# audio_board.net
KiCad netlist of a schematic drawn in EAGLE
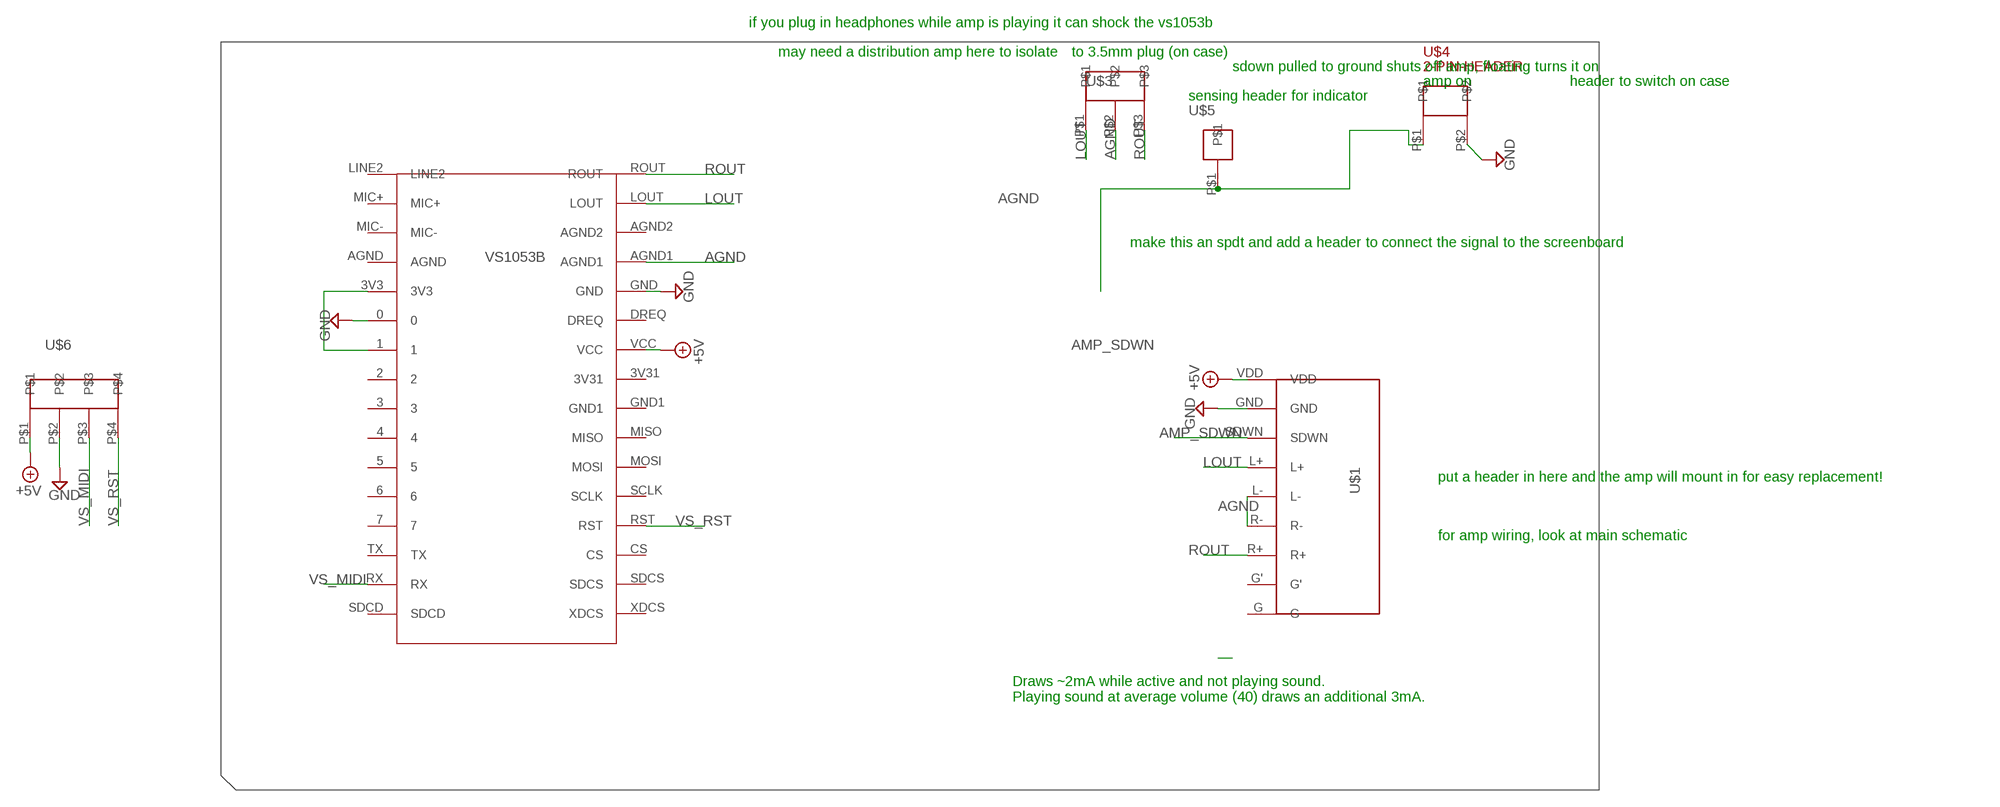
[diagram p0: schematic, sheet 1]

(export (version "E")
  (design (tool "Eeschema 10.0.6"))
  (components
    (comp (ref "U$1")
      (value "AUDIOAMP")
      (footprint "eagle-import:AUDIOAMP")
      (libsource (lib "eagle-import") (part "AUDIOAMP"))
    )
    (comp (ref "U$3")
      (value "3-PIN-HEADER")
      (footprint "eagle-import:3-PIN-HEADER")
      (libsource (lib "eagle-import") (part "3-PIN-HEADER"))
    )
    (comp (ref "U$4")
      (value "2-PIN-HEADER")
      (footprint "eagle-import:2-PIN-HEADER")
      (libsource (lib "eagle-import") (part "2-PIN-HEADER"))
    )
    (comp (ref "U$5")
      (value "1-PIN-HEADER")
      (footprint "eagle-import:1-PIN-HEADER")
      (libsource (lib "eagle-import") (part "1-PIN-HEADER"))
    )
    (comp (ref "U$6")
      (value "4-PIN-HEADER")
      (footprint "eagle-import:4-PIN-HEADER")
      (libsource (lib "eagle-import") (part "4-PIN-HEADER"))
    )
    (comp (ref "VS1053B")
      (value "VS1053B")
      (footprint "eagle-import:VS1053B")
      (libsource (lib "eagle-import") (part "VS1053B"))
    )
  )
  (nets
    (net (code "1") (name "+5V") (class "Default")
      (node (ref "U$1") (pin "VDD") (pinfunction "VDD_VDD") (pintype "bidirectional"))
      (node (ref "U$6") (pin "P$1") (pinfunction "P$1_P$1") (pintype "bidirectional"))
      (node (ref "VS1053B") (pin "VCC") (pinfunction "VCC_VCC") (pintype "bidirectional"))
    )
    (net (code "2") (name "/AGND") (class "Default")
      (node (ref "U$1") (pin "L-") (pinfunction "L-_L-") (pintype "bidirectional"))
      (node (ref "U$1") (pin "R-") (pinfunction "R-_R-") (pintype "bidirectional"))
      (node (ref "U$3") (pin "P$2") (pinfunction "P$2_P$2") (pintype "bidirectional"))
      (node (ref "VS1053B") (pin "AGND1") (pinfunction "AGND1_AGND1") (pintype "bidirectional"))
    )
    (net (code "3") (name "/AMP_SDWN") (class "Default")
      (node (ref "U$1") (pin "SDWN") (pinfunction "SDWN_SDWN") (pintype "bidirectional"))
      (node (ref "U$4") (pin "P$1") (pinfunction "P$1_P$1") (pintype "bidirectional"))
      (node (ref "U$5") (pin "P$1") (pinfunction "P$1_P$1") (pintype "bidirectional"))
    )
    (net (code "4") (name "/LOUT") (class "Default")
      (node (ref "U$1") (pin "L+") (pinfunction "L+_L+") (pintype "bidirectional"))
      (node (ref "U$3") (pin "P$1") (pinfunction "P$1_P$1") (pintype "bidirectional"))
      (node (ref "VS1053B") (pin "LOUT") (pinfunction "LOUT_LOUT") (pintype "bidirectional"))
    )
    (net (code "5") (name "/ROUT") (class "Default")
      (node (ref "U$1") (pin "R+") (pinfunction "R+_R+") (pintype "bidirectional"))
      (node (ref "U$3") (pin "P$3") (pinfunction "P$3_P$3") (pintype "bidirectional"))
      (node (ref "VS1053B") (pin "ROUT") (pinfunction "ROUT_ROUT") (pintype "bidirectional"))
    )
    (net (code "6") (name "/VS_MIDI") (class "Default")
      (node (ref "U$6") (pin "P$3") (pinfunction "P$3_P$3") (pintype "bidirectional"))
      (node (ref "VS1053B") (pin "RX") (pinfunction "RX_RX") (pintype "bidirectional"))
    )
    (net (code "7") (name "/VS_RST") (class "Default")
      (node (ref "U$6") (pin "P$4") (pinfunction "P$4_P$4") (pintype "bidirectional"))
      (node (ref "VS1053B") (pin "RST") (pinfunction "RST_RST") (pintype "bidirectional"))
    )
    (net (code "8") (name "GND") (class "Default")
      (node (ref "U$1") (pin "GND") (pinfunction "GND_GND") (pintype "bidirectional"))
      (node (ref "U$4") (pin "P$2") (pinfunction "P$2_P$2") (pintype "bidirectional"))
      (node (ref "U$6") (pin "P$2") (pinfunction "P$2_P$2") (pintype "bidirectional"))
      (node (ref "VS1053B") (pin "0") (pinfunction "0_0") (pintype "bidirectional"))
      (node (ref "VS1053B") (pin "GND") (pinfunction "GND_GND") (pintype "bidirectional"))
    )
    (net (code "9") (name "Net-(VS1053B-Pad1)") (class "Default")
      (node (ref "VS1053B") (pin "1") (pinfunction "1_1") (pintype "bidirectional"))
      (node (ref "VS1053B") (pin "3V3") (pinfunction "3V3_3V3") (pintype "bidirectional"))
    )
    (net (code "10") (name "unconnected-(U$1-PadG')") (class "Default")
      (node (ref "U$1") (pin "G'") (pinfunction "G'_G'") (pintype "bidirectional"))
    )
    (net (code "11") (name "unconnected-(U$1-PadG)") (class "Default")
      (node (ref "U$1") (pin "G") (pinfunction "G_G") (pintype "bidirectional"))
    )
    (net (code "12") (name "unconnected-(VS1053B-Pad2)") (class "Default")
      (node (ref "VS1053B") (pin "2") (pinfunction "2_2") (pintype "bidirectional"))
    )
    (net (code "13") (name "unconnected-(VS1053B-Pad3)") (class "Default")
      (node (ref "VS1053B") (pin "3") (pinfunction "3_3") (pintype "bidirectional"))
    )
    (net (code "14") (name "unconnected-(VS1053B-Pad3V31)") (class "Default")
      (node (ref "VS1053B") (pin "3V31") (pinfunction "3V31_3V31") (pintype "bidirectional"))
    )
    (net (code "15") (name "unconnected-(VS1053B-Pad4)") (class "Default")
      (node (ref "VS1053B") (pin "4") (pinfunction "4_4") (pintype "bidirectional"))
    )
    (net (code "16") (name "unconnected-(VS1053B-Pad5)") (class "Default")
      (node (ref "VS1053B") (pin "5") (pinfunction "5_5") (pintype "bidirectional"))
    )
    (net (code "17") (name "unconnected-(VS1053B-Pad6)") (class "Default")
      (node (ref "VS1053B") (pin "6") (pinfunction "6_6") (pintype "bidirectional"))
    )
    (net (code "18") (name "unconnected-(VS1053B-Pad7)") (class "Default")
      (node (ref "VS1053B") (pin "7") (pinfunction "7_7") (pintype "bidirectional"))
    )
    (net (code "19") (name "unconnected-(VS1053B-PadAGND)") (class "Default")
      (node (ref "VS1053B") (pin "AGND") (pinfunction "AGND_AGND") (pintype "bidirectional"))
    )
    (net (code "20") (name "unconnected-(VS1053B-PadAGND2)") (class "Default")
      (node (ref "VS1053B") (pin "AGND2") (pinfunction "AGND2_AGND2") (pintype "bidirectional"))
    )
    (net (code "21") (name "unconnected-(VS1053B-PadCS)") (class "Default")
      (node (ref "VS1053B") (pin "CS") (pinfunction "CS_CS") (pintype "bidirectional"))
    )
    (net (code "22") (name "unconnected-(VS1053B-PadDREQ)") (class "Default")
      (node (ref "VS1053B") (pin "DREQ") (pinfunction "DREQ_DREQ") (pintype "bidirectional"))
    )
    (net (code "23") (name "unconnected-(VS1053B-PadGND1)") (class "Default")
      (node (ref "VS1053B") (pin "GND1") (pinfunction "GND1_GND1") (pintype "bidirectional"))
    )
    (net (code "24") (name "unconnected-(VS1053B-PadLINE2)") (class "Default")
      (node (ref "VS1053B") (pin "LINE2") (pinfunction "LINE2_LINE2") (pintype "bidirectional"))
    )
    (net (code "25") (name "unconnected-(VS1053B-PadMIC+)") (class "Default")
      (node (ref "VS1053B") (pin "MIC+") (pinfunction "MIC+_MIC+") (pintype "bidirectional"))
    )
    (net (code "26") (name "unconnected-(VS1053B-PadMIC-)") (class "Default")
      (node (ref "VS1053B") (pin "MIC-") (pinfunction "MIC-_MIC-") (pintype "bidirectional"))
    )
    (net (code "27") (name "unconnected-(VS1053B-PadMISO)") (class "Default")
      (node (ref "VS1053B") (pin "MISO") (pinfunction "MISO_MISO") (pintype "bidirectional"))
    )
    (net (code "28") (name "unconnected-(VS1053B-PadMOSI)") (class "Default")
      (node (ref "VS1053B") (pin "MOSI") (pinfunction "MOSI_MOSI") (pintype "bidirectional"))
    )
    (net (code "29") (name "unconnected-(VS1053B-PadSCLK)") (class "Default")
      (node (ref "VS1053B") (pin "SCLK") (pinfunction "SCLK_SCLK") (pintype "bidirectional"))
    )
    (net (code "30") (name "unconnected-(VS1053B-PadSDCD)") (class "Default")
      (node (ref "VS1053B") (pin "SDCD") (pinfunction "SDCD_SDCD") (pintype "bidirectional"))
    )
    (net (code "31") (name "unconnected-(VS1053B-PadSDCS)") (class "Default")
      (node (ref "VS1053B") (pin "SDCS") (pinfunction "SDCS_SDCS") (pintype "bidirectional"))
    )
    (net (code "32") (name "unconnected-(VS1053B-PadTX)") (class "Default")
      (node (ref "VS1053B") (pin "TX") (pinfunction "TX_TX") (pintype "bidirectional"))
    )
    (net (code "33") (name "unconnected-(VS1053B-PadXDCS)") (class "Default")
      (node (ref "VS1053B") (pin "XDCS") (pinfunction "XDCS_XDCS") (pintype "bidirectional"))
    )
  )
)
